# NMEA_Temperatursensor.net
KiCad netlist of a schematic drawn in EAGLE
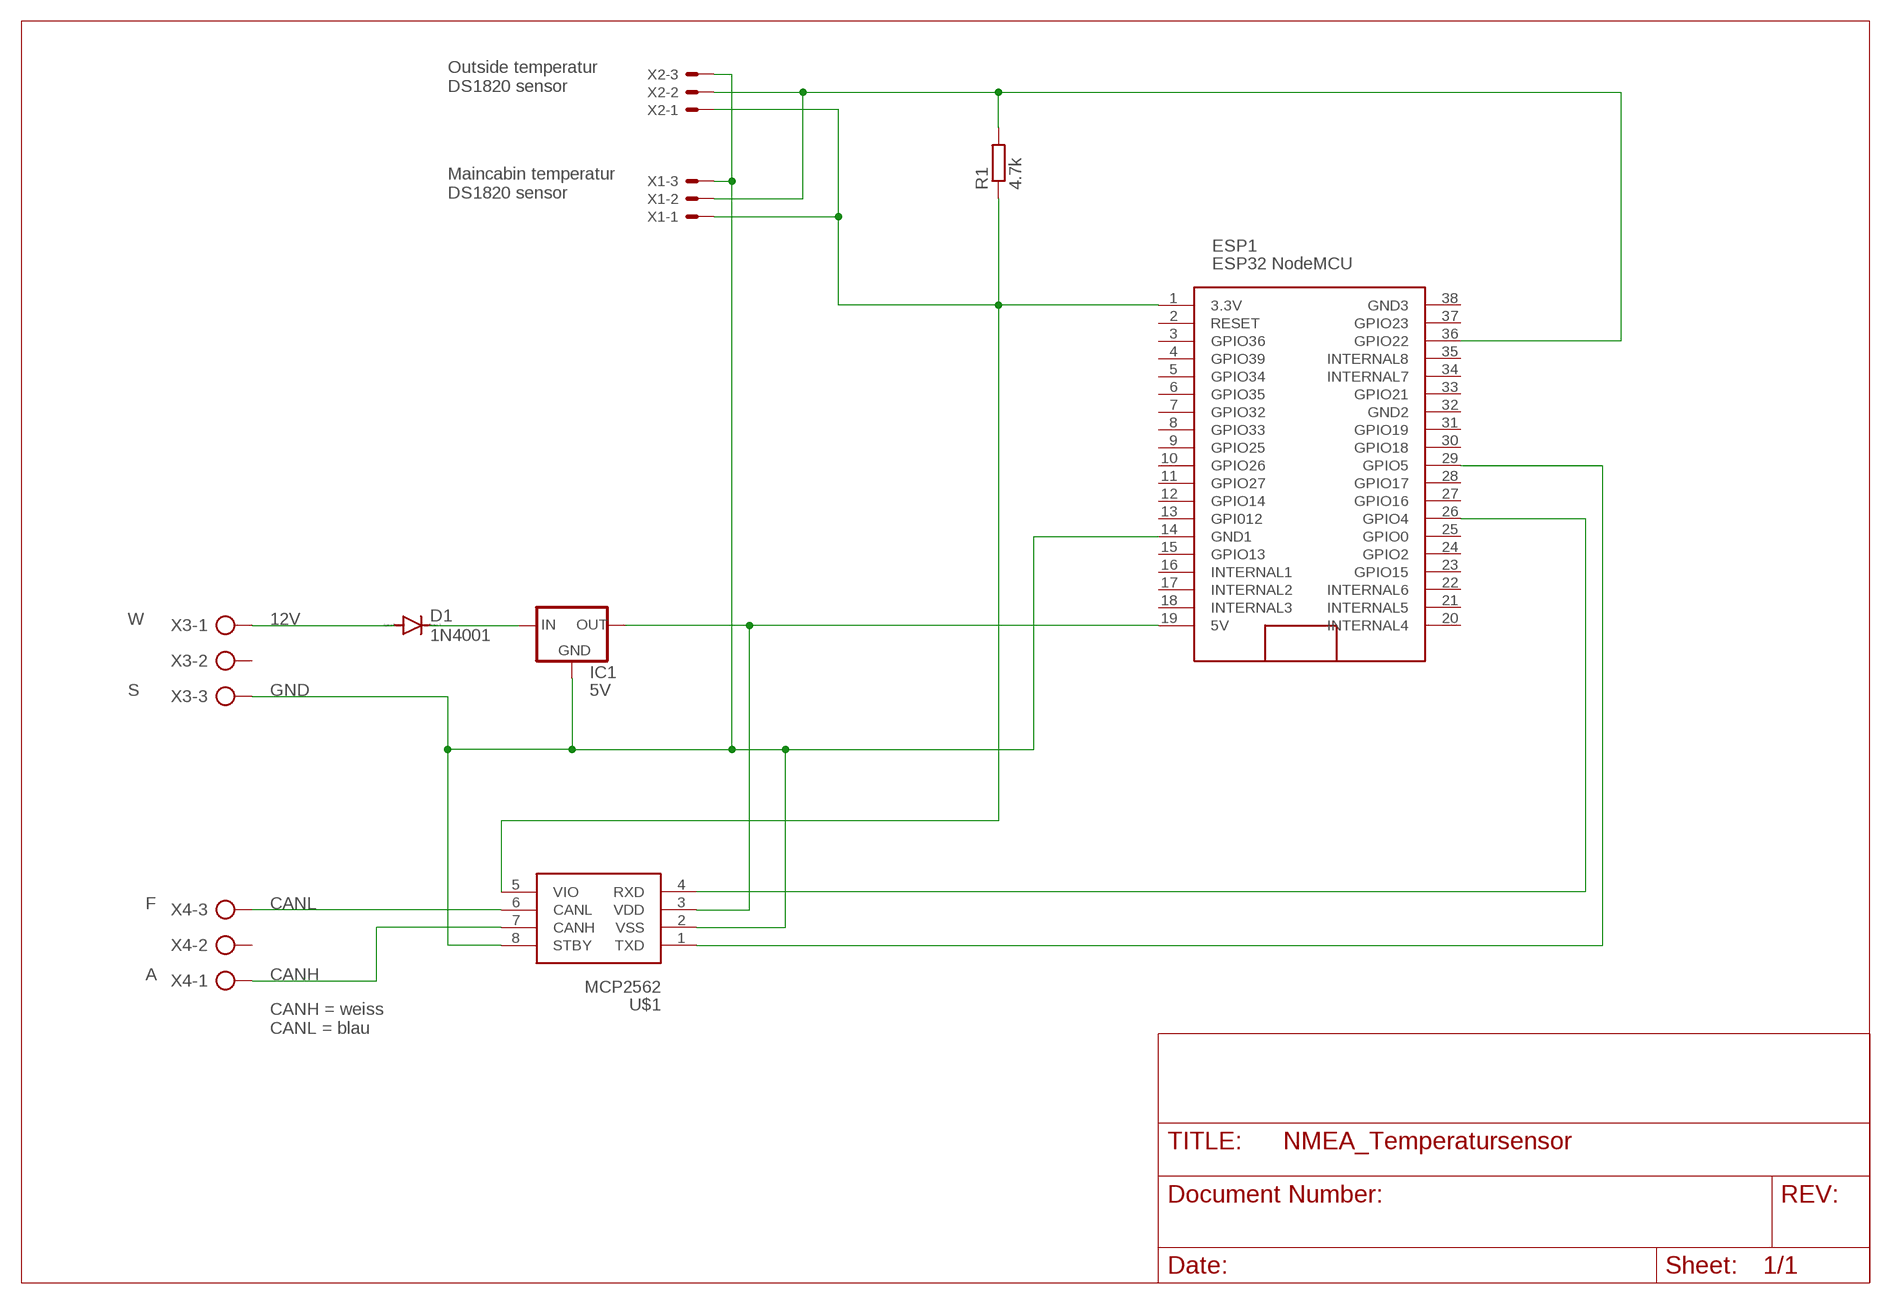
[diagram p0: schematic, sheet 1]

(export (version "E")
  (design (tool "Eeschema 10.0.6"))
  (components
    (comp (ref "D1")
      (value "1N4001")
      (footprint "eagle-import:DO41-10")
      (libsource (lib "eagle-import") (part "1N4004"))
    )
    (comp (ref "ESP1")
      (value "ESP32 NodeMCU")
      (footprint "eagle-import:ESP32_NODEMCU")
      (libsource (lib "eagle-import") (part "ESP32-NODEMCU"))
    )
    (comp (ref "IC1")
      (value "5V")
      (footprint "eagle-import:78XXS")
      (libsource (lib "eagle-import") (part "78XXS"))
    )
    (comp (ref "R1")
      (value "4.7k")
      (footprint "eagle-import:0204_7")
      (libsource (lib "eagle-import") (part "R-EU_0204/7"))
    )
    (comp (ref "U$1")
      (value "MCP2562")
      (footprint "eagle-import:DIL08")
      (libsource (lib "eagle-import") (part "MCP2562"))
    )
    (comp (ref "X1")
      (value "22-23-2031")
      (footprint "eagle-import:22-23-2031")
      (fields (field (name "MF") "MOLEX"))
      (libsource (lib "eagle-import") (part "22-23-2031"))
    )
    (comp (ref "X2")
      (value "22-23-2031")
      (footprint "eagle-import:22-23-2031")
      (fields (field (name "MF") "MOLEX"))
      (libsource (lib "eagle-import") (part "22-23-2031"))
    )
    (comp (ref "X3")
      (value "AK300/3")
      (footprint "eagle-import:AK300_3")
      (libsource (lib "eagle-import") (part "AK300/3"))
    )
    (comp (ref "X4")
      (value "AK300/3")
      (footprint "eagle-import:AK300_3")
      (libsource (lib "eagle-import") (part "AK300/3"))
    )
  )
  (nets
    (net (code "1") (name "/12V") (class "Default")
      (node (ref "D1") (pin "A") (pinfunction "A_A") (pintype "passive"))
      (node (ref "X3") (pin "1") (pinfunction "KL_1") (pintype "passive"))
    )
    (net (code "2") (name "/CANH") (class "Default")
      (node (ref "U$1") (pin "7") (pinfunction "CANH_7") (pintype "bidirectional"))
      (node (ref "X4") (pin "1") (pinfunction "KL_1") (pintype "passive"))
    )
    (net (code "3") (name "/CANL") (class "Default")
      (node (ref "U$1") (pin "6") (pinfunction "CANL_6") (pintype "bidirectional"))
      (node (ref "X4") (pin "3") (pinfunction "KL_3") (pintype "passive"))
    )
    (net (code "4") (name "/GND") (class "Default")
      (node (ref "ESP1") (pin "14") (pinfunction "GND1_14") (pintype "power_in"))
      (node (ref "IC1") (pin "GND") (pinfunction "GND_GND") (pintype "input"))
      (node (ref "U$1") (pin "2") (pinfunction "VSS_2") (pintype "bidirectional"))
      (node (ref "U$1") (pin "8") (pinfunction "STBY_8") (pintype "bidirectional"))
      (node (ref "X1") (pin "3") (pinfunction "S_3") (pintype "passive"))
      (node (ref "X2") (pin "3") (pinfunction "S_3") (pintype "passive"))
      (node (ref "X3") (pin "3") (pinfunction "KL_3") (pintype "passive"))
    )
    (net (code "5") (name "/GND2") (class "Default")
      (node (ref "ESP1") (pin "32") (pinfunction "GND2_32") (pintype "power_in"))
    )
    (net (code "6") (name "/GND3") (class "Default")
      (node (ref "ESP1") (pin "38") (pinfunction "GND3_38") (pintype "power_in"))
    )
    (net (code "7") (name "Net-(D1-PadC)") (class "Default")
      (node (ref "D1") (pin "C") (pinfunction "C_C") (pintype "passive"))
      (node (ref "IC1") (pin "IN") (pinfunction "IN_IN") (pintype "input"))
    )
    (net (code "8") (name "Net-(ESP1-3.3V)") (class "Default")
      (node (ref "ESP1") (pin "1") (pinfunction "3.3V_1") (pintype "power_in"))
      (node (ref "R1") (pin "1") (pinfunction "1_1") (pintype "passive"))
      (node (ref "U$1") (pin "5") (pinfunction "VIO_5") (pintype "bidirectional"))
      (node (ref "X1") (pin "1") (pinfunction "S_1") (pintype "passive"))
      (node (ref "X2") (pin "1") (pinfunction "S_1") (pintype "passive"))
    )
    (net (code "9") (name "Net-(ESP1-5V)") (class "Default")
      (node (ref "ESP1") (pin "19") (pinfunction "5V_19") (pintype "power_in"))
      (node (ref "IC1") (pin "OUT") (pinfunction "OUT_OUT") (pintype "passive"))
      (node (ref "U$1") (pin "3") (pinfunction "VDD_3") (pintype "bidirectional"))
    )
    (net (code "10") (name "Net-(ESP1-GPIO4)") (class "Default")
      (node (ref "ESP1") (pin "26") (pinfunction "GPIO4_26") (pintype "bidirectional"))
      (node (ref "U$1") (pin "4") (pinfunction "RXD_4") (pintype "bidirectional"))
    )
    (net (code "11") (name "Net-(ESP1-GPIO5)") (class "Default")
      (node (ref "ESP1") (pin "29") (pinfunction "GPIO5_29") (pintype "bidirectional"))
      (node (ref "U$1") (pin "1") (pinfunction "TXD_1") (pintype "bidirectional"))
    )
    (net (code "12") (name "Net-(ESP1-GPIO22)") (class "Default")
      (node (ref "ESP1") (pin "36") (pinfunction "GPIO22_36") (pintype "bidirectional"))
      (node (ref "R1") (pin "2") (pinfunction "2_2") (pintype "passive"))
      (node (ref "X1") (pin "2") (pinfunction "S_2") (pintype "passive"))
      (node (ref "X2") (pin "2") (pinfunction "S_2") (pintype "passive"))
    )
    (net (code "13") (name "unconnected-(ESP1-GPI012-Pad13)") (class "Default")
      (node (ref "ESP1") (pin "13") (pinfunction "GPI012_13") (pintype "bidirectional"))
    )
    (net (code "14") (name "unconnected-(ESP1-GPIO0-Pad25)") (class "Default")
      (node (ref "ESP1") (pin "25") (pinfunction "GPIO0_25") (pintype "output"))
    )
    (net (code "15") (name "unconnected-(ESP1-GPIO2-Pad24)") (class "Default")
      (node (ref "ESP1") (pin "24") (pinfunction "GPIO2_24") (pintype "bidirectional"))
    )
    (net (code "16") (name "unconnected-(ESP1-GPIO13-Pad15)") (class "Default")
      (node (ref "ESP1") (pin "15") (pinfunction "GPIO13_15") (pintype "bidirectional"))
    )
    (net (code "17") (name "unconnected-(ESP1-GPIO14-Pad12)") (class "Default")
      (node (ref "ESP1") (pin "12") (pinfunction "GPIO14_12") (pintype "bidirectional"))
    )
    (net (code "18") (name "unconnected-(ESP1-GPIO15-Pad23)") (class "Default")
      (node (ref "ESP1") (pin "23") (pinfunction "GPIO15_23") (pintype "bidirectional"))
    )
    (net (code "19") (name "unconnected-(ESP1-GPIO16-Pad27)") (class "Default")
      (node (ref "ESP1") (pin "27") (pinfunction "GPIO16_27") (pintype "bidirectional"))
    )
    (net (code "20") (name "unconnected-(ESP1-GPIO17-Pad28)") (class "Default")
      (node (ref "ESP1") (pin "28") (pinfunction "GPIO17_28") (pintype "bidirectional"))
    )
    (net (code "21") (name "unconnected-(ESP1-GPIO18-Pad30)") (class "Default")
      (node (ref "ESP1") (pin "30") (pinfunction "GPIO18_30") (pintype "bidirectional"))
    )
    (net (code "22") (name "unconnected-(ESP1-GPIO19-Pad31)") (class "Default")
      (node (ref "ESP1") (pin "31") (pinfunction "GPIO19_31") (pintype "bidirectional"))
    )
    (net (code "23") (name "unconnected-(ESP1-GPIO21-Pad33)") (class "Default")
      (node (ref "ESP1") (pin "33") (pinfunction "GPIO21_33") (pintype "bidirectional"))
    )
    (net (code "24") (name "unconnected-(ESP1-GPIO23-Pad37)") (class "Default")
      (node (ref "ESP1") (pin "37") (pinfunction "GPIO23_37") (pintype "bidirectional"))
    )
    (net (code "25") (name "unconnected-(ESP1-GPIO25-Pad9)") (class "Default")
      (node (ref "ESP1") (pin "9") (pinfunction "GPIO25_9") (pintype "bidirectional"))
    )
    (net (code "26") (name "unconnected-(ESP1-GPIO26-Pad10)") (class "Default")
      (node (ref "ESP1") (pin "10") (pinfunction "GPIO26_10") (pintype "bidirectional"))
    )
    (net (code "27") (name "unconnected-(ESP1-GPIO27-Pad11)") (class "Default")
      (node (ref "ESP1") (pin "11") (pinfunction "GPIO27_11") (pintype "bidirectional"))
    )
    (net (code "28") (name "unconnected-(ESP1-GPIO32-Pad7)") (class "Default")
      (node (ref "ESP1") (pin "7") (pinfunction "GPIO32_7") (pintype "bidirectional"))
    )
    (net (code "29") (name "unconnected-(ESP1-GPIO33-Pad8)") (class "Default")
      (node (ref "ESP1") (pin "8") (pinfunction "GPIO33_8") (pintype "bidirectional"))
    )
    (net (code "30") (name "unconnected-(ESP1-GPIO34-Pad5)") (class "Default")
      (node (ref "ESP1") (pin "5") (pinfunction "GPIO34_5") (pintype "input"))
    )
    (net (code "31") (name "unconnected-(ESP1-GPIO35-Pad6)") (class "Default")
      (node (ref "ESP1") (pin "6") (pinfunction "GPIO35_6") (pintype "input"))
    )
    (net (code "32") (name "unconnected-(ESP1-GPIO36-Pad3)") (class "Default")
      (node (ref "ESP1") (pin "3") (pinfunction "GPIO36_3") (pintype "input"))
    )
    (net (code "33") (name "unconnected-(ESP1-GPIO39-Pad4)") (class "Default")
      (node (ref "ESP1") (pin "4") (pinfunction "GPIO39_4") (pintype "input"))
    )
    (net (code "34") (name "unconnected-(ESP1-INTERNAL1-Pad16)") (class "Default")
      (node (ref "ESP1") (pin "16") (pinfunction "INTERNAL1_16") (pintype "no_connect"))
    )
    (net (code "35") (name "unconnected-(ESP1-INTERNAL2-Pad17)") (class "Default")
      (node (ref "ESP1") (pin "17") (pinfunction "INTERNAL2_17") (pintype "no_connect"))
    )
    (net (code "36") (name "unconnected-(ESP1-INTERNAL3-Pad18)") (class "Default")
      (node (ref "ESP1") (pin "18") (pinfunction "INTERNAL3_18") (pintype "no_connect"))
    )
    (net (code "37") (name "unconnected-(ESP1-INTERNAL4-Pad20)") (class "Default")
      (node (ref "ESP1") (pin "20") (pinfunction "INTERNAL4_20") (pintype "no_connect"))
    )
    (net (code "38") (name "unconnected-(ESP1-INTERNAL5-Pad21)") (class "Default")
      (node (ref "ESP1") (pin "21") (pinfunction "INTERNAL5_21") (pintype "no_connect"))
    )
    (net (code "39") (name "unconnected-(ESP1-INTERNAL6-Pad22)") (class "Default")
      (node (ref "ESP1") (pin "22") (pinfunction "INTERNAL6_22") (pintype "no_connect"))
    )
    (net (code "40") (name "unconnected-(ESP1-INTERNAL7-Pad34)") (class "Default")
      (node (ref "ESP1") (pin "34") (pinfunction "INTERNAL7_34") (pintype "no_connect"))
    )
    (net (code "41") (name "unconnected-(ESP1-INTERNAL8-Pad35)") (class "Default")
      (node (ref "ESP1") (pin "35") (pinfunction "INTERNAL8_35") (pintype "no_connect"))
    )
    (net (code "42") (name "unconnected-(ESP1-RESET-Pad2)") (class "Default")
      (node (ref "ESP1") (pin "2") (pinfunction "RESET_2") (pintype "input"))
    )
    (net (code "43") (name "unconnected-(X3B-KL-Pad2)") (class "Default")
      (node (ref "X3") (pin "2") (pinfunction "KL_2") (pintype "passive"))
    )
    (net (code "44") (name "unconnected-(X4B-KL-Pad2)") (class "Default")
      (node (ref "X4") (pin "2") (pinfunction "KL_2") (pintype "passive"))
    )
  )
)
